# switchreg.net
KiCad netlist of a schematic drawn in Altium Designer
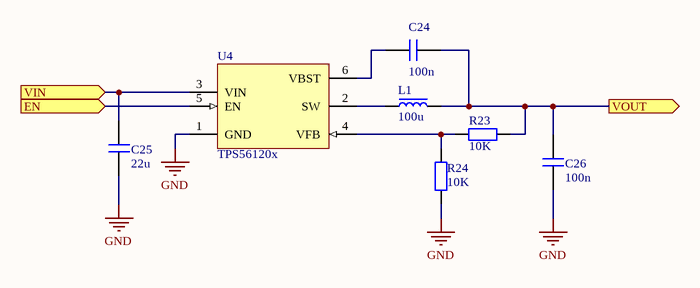
[diagram p0: switchreg.SchDoc]

(export (version "E")
  (design (tool "Eeschema 10.0.6"))
  (components
    (comp (ref "C24")
      (value "100n")
      (footprint "CAPC1005X06N")
      (description "Capacitor")
      (fields (field (name "Comment") "cap"))
      (libsource (lib "lib_passives") (part "cap"))
    )
    (comp (ref "C25")
      (value "22u")
      (footprint "CAPC2012X11N")
      (description "Capacitor")
      (fields (field (name "Comment") "cap"))
      (libsource (lib "lib_passives") (part "cap"))
    )
    (comp (ref "C26")
      (value "100n")
      (footprint "CAPC2012X11N")
      (description "Capacitor")
      (fields (field (name "Comment") "cap"))
      (libsource (lib "lib_passives") (part "cap"))
    )
    (comp (ref "L1")
      (value "100u")
      (footprint "INDC4040X18N")
      (description "Inductor")
      (fields (field (name "Comment") "inds"))
      (libsource (lib "lib_passives") (part "inds"))
    )
    (comp (ref "R23")
      (value "10K")
      (footprint "RESC1005X04N")
      (description "Resistor")
      (fields (field (name "Comment") "res"))
      (libsource (lib "") (part "res_1"))
    )
    (comp (ref "R24")
      (value "10K")
      (footprint "RESC1005X04N")
      (description "Resistor")
      (fields (field (name "Comment") "res"))
      (libsource (lib "lib_passives") (part "res"))
    )
    (comp (ref "U4")
      (value "TPS56120x")
      (footprint "SOT95P280X110-6N")
      (description "4.5-V to 17-V Input, 1-A Synchronous  Step-Down  Voltage  Regulator  in 6-Pin  SOT-23")
      (libsource (lib "lib_ti") (part "tps56120x"))
    )
  )
  (nets
    (net (code "1") (name "/EN") (class "Default")
      (node (ref "U4") (pin "5") (pinfunction "EN_5") (pintype "input"))
    )
    (net (code "2") (name "/VIN") (class "Default")
      (node (ref "C25") (pin "2") (pinfunction "2_2") (pintype "passive"))
      (node (ref "U4") (pin "3") (pinfunction "VIN_3") (pintype "power_in"))
    )
    (net (code "3") (name "/VOUT") (class "Default")
      (node (ref "C24") (pin "2") (pinfunction "2_2") (pintype "passive"))
      (node (ref "C26") (pin "2") (pinfunction "2_2") (pintype "passive"))
      (node (ref "L1") (pin "2") (pinfunction "2_2") (pintype "passive"))
      (node (ref "R23") (pin "2") (pinfunction "2_2") (pintype "passive"))
    )
    (net (code "4") (name "GND") (class "Default")
      (node (ref "C25") (pin "1") (pinfunction "1_1") (pintype "passive"))
      (node (ref "C26") (pin "1") (pinfunction "1_1") (pintype "passive"))
      (node (ref "R24") (pin "1") (pinfunction "1_1") (pintype "passive"))
      (node (ref "U4") (pin "1") (pinfunction "GND_1") (pintype "power_in"))
    )
    (net (code "5") (name "Net-(U4-SW)") (class "Default")
      (node (ref "L1") (pin "1") (pinfunction "1_1") (pintype "passive"))
      (node (ref "U4") (pin "2") (pinfunction "SW_2") (pintype "power_in"))
    )
    (net (code "6") (name "Net-(U4-VBST)") (class "Default")
      (node (ref "C24") (pin "1") (pinfunction "1_1") (pintype "passive"))
      (node (ref "U4") (pin "6") (pinfunction "VBST_6") (pintype "passive"))
    )
    (net (code "7") (name "Net-(U4-VFB)") (class "Default")
      (node (ref "R23") (pin "1") (pinfunction "1_1") (pintype "passive"))
      (node (ref "R24") (pin "2") (pinfunction "2_2") (pintype "passive"))
      (node (ref "U4") (pin "4") (pinfunction "VFB_4") (pintype "input"))
    )
  )
)
